# tivac-shield-communication.net
KiCad netlist of a schematic drawn in EAGLE
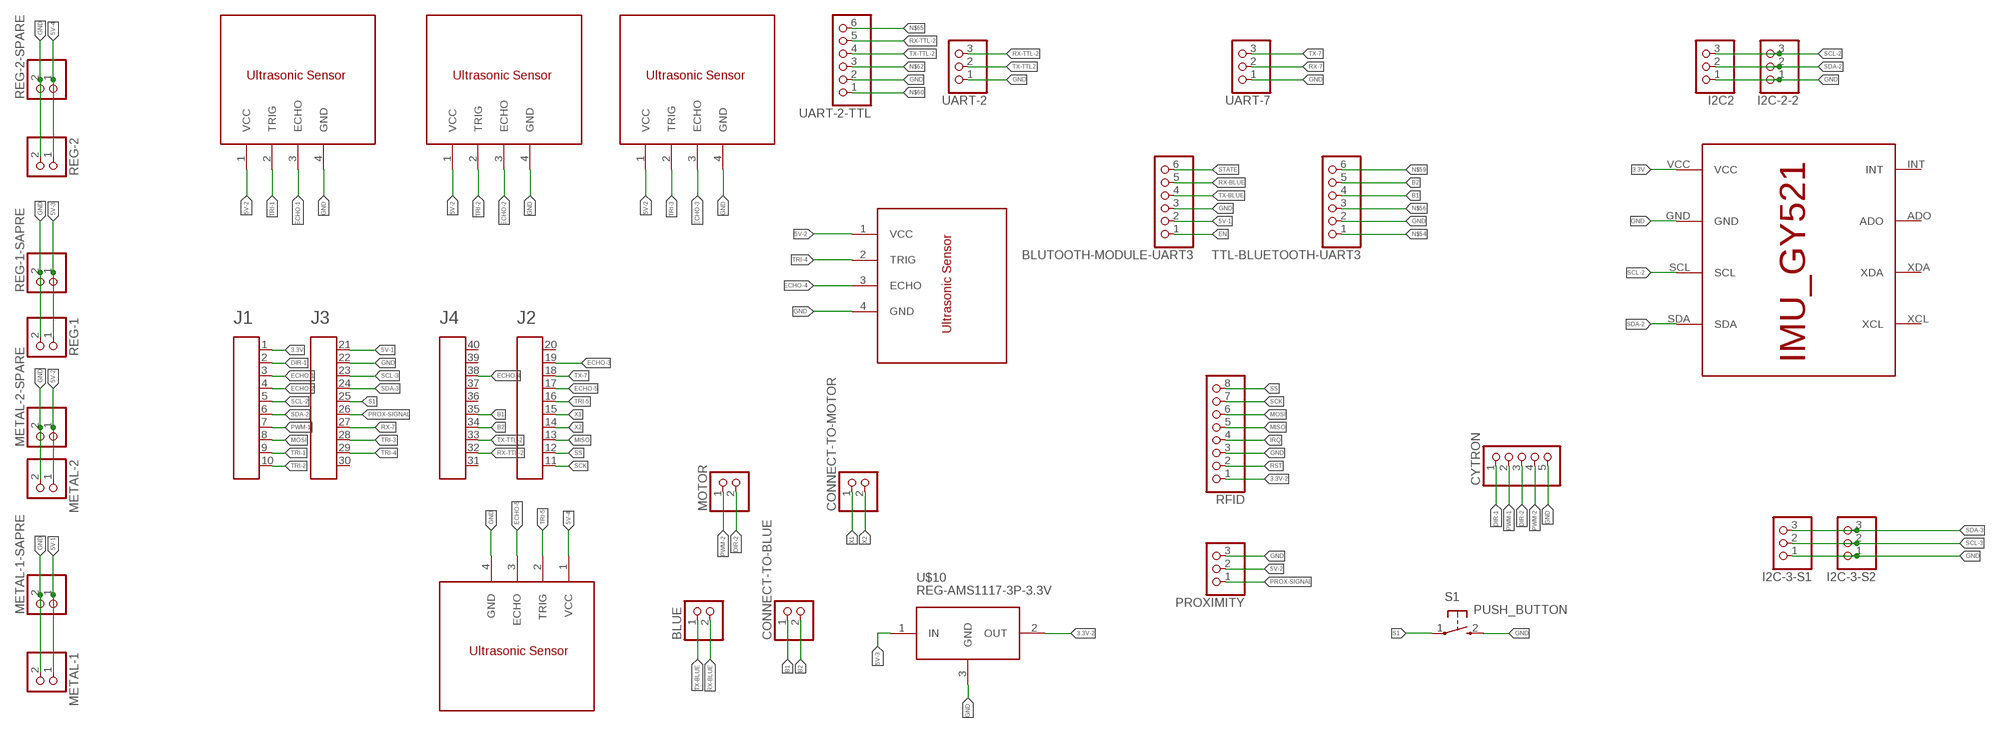
[diagram p0: schematic, sheet 1]

(export (version "E")
  (design (tool "Eeschema 10.0.6"))
  (components
    (comp (ref "A1")
      (value "HEADER4X10-BOOSTERPACK")
      (footprint "eagle-import:4X10-BOOSTERPACK")
      (libsource (lib "eagle-import") (part "HEADER4X10-BOOSTERPACK"))
    )
    (comp (ref "BLUE")
      (value "PINHD-2_DATA")
      (footprint "eagle-import:1X02_DATA")
      (libsource (lib "eagle-import") (part "PINHD-2_DATA"))
    )
    (comp (ref "BLUTOOTH-MODULE-UART3")
      (value "PINHD-1X6")
      (footprint "eagle-import:1X06")
      (libsource (lib "eagle-import") (part "PINHD-1X6"))
    )
    (comp (ref "CONNECT-TO-BLUE")
      (value "PINHD-2_DATA")
      (footprint "eagle-import:1X02_DATA")
      (libsource (lib "eagle-import") (part "PINHD-2_DATA"))
    )
    (comp (ref "CONNECT-TO-MOTOR")
      (value "PINHD-2_DATA")
      (footprint "eagle-import:1X02_DATA")
      (libsource (lib "eagle-import") (part "PINHD-2_DATA"))
    )
    (comp (ref "CYTRON")
      (value "PINHD-5_DATA")
      (footprint "eagle-import:1X05_DATA")
      (libsource (lib "eagle-import") (part "PINHD-5_DATA"))
    )
    (comp (ref "I2C-2-2")
      (value "PINHD-1X3")
      (footprint "eagle-import:1X03")
      (libsource (lib "eagle-import") (part "PINHD-1X3"))
    )
    (comp (ref "I2C-3-S1")
      (value "PINHD-1X3")
      (footprint "eagle-import:1X03")
      (libsource (lib "eagle-import") (part "PINHD-1X3"))
    )
    (comp (ref "I2C-3-S2")
      (value "PINHD-1X3")
      (footprint "eagle-import:1X03")
      (libsource (lib "eagle-import") (part "PINHD-1X3"))
    )
    (comp (ref "I2C2")
      (value "PINHD-1X3")
      (footprint "eagle-import:1X03")
      (libsource (lib "eagle-import") (part "PINHD-1X3"))
    )
    (comp (ref "METAL-1")
      (value "PINHD-1X2")
      (footprint "eagle-import:1X02")
      (libsource (lib "eagle-import") (part "PINHD-1X2"))
    )
    (comp (ref "METAL-1-SAPRE")
      (value "PINHD-1X2")
      (footprint "eagle-import:1X02")
      (libsource (lib "eagle-import") (part "PINHD-1X2"))
    )
    (comp (ref "METAL-2")
      (value "PINHD-1X2")
      (footprint "eagle-import:1X02")
      (libsource (lib "eagle-import") (part "PINHD-1X2"))
    )
    (comp (ref "METAL-2-SPARE")
      (value "PINHD-1X2")
      (footprint "eagle-import:1X02")
      (libsource (lib "eagle-import") (part "PINHD-1X2"))
    )
    (comp (ref "MOTOR")
      (value "PINHD-2_DATA")
      (footprint "eagle-import:1X02_DATA")
      (libsource (lib "eagle-import") (part "PINHD-2_DATA"))
    )
    (comp (ref "PROXIMITY")
      (value "PINHD-1X3")
      (footprint "eagle-import:1X03")
      (libsource (lib "eagle-import") (part "PINHD-1X3"))
    )
    (comp (ref "REG-1")
      (value "PINHD-1X2")
      (footprint "eagle-import:1X02")
      (libsource (lib "eagle-import") (part "PINHD-1X2"))
    )
    (comp (ref "REG-1-SAPRE")
      (value "PINHD-1X2")
      (footprint "eagle-import:1X02")
      (libsource (lib "eagle-import") (part "PINHD-1X2"))
    )
    (comp (ref "REG-2")
      (value "PINHD-1X2")
      (footprint "eagle-import:1X02")
      (libsource (lib "eagle-import") (part "PINHD-1X2"))
    )
    (comp (ref "REG-2-SPARE")
      (value "PINHD-1X2")
      (footprint "eagle-import:1X02")
      (libsource (lib "eagle-import") (part "PINHD-1X2"))
    )
    (comp (ref "RFID")
      (value "PINHD-1X8")
      (footprint "eagle-import:1X08")
      (libsource (lib "eagle-import") (part "PINHD-1X8"))
    )
    (comp (ref "S1")
      (value "PUSH_BUTTON")
      (footprint "eagle-import:B3F-10XX")
      (libsource (lib "eagle-import") (part "PUSH_BUTTON"))
    )
    (comp (ref "TTL-BLUETOOTH-UART3")
      (value "PINHD-6_DATA")
      (footprint "eagle-import:1X06_DATA")
      (libsource (lib "eagle-import") (part "PINHD-6_DATA"))
    )
    (comp (ref "U$1")
      (value "ULTRASONIC_SENSOR")
      (footprint "eagle-import:1X04")
      (libsource (lib "eagle-import") (part "ULTRASONIC_SENSOR"))
    )
    (comp (ref "U$2")
      (value "ULTRASONIC_SENSOR")
      (footprint "eagle-import:1X04")
      (libsource (lib "eagle-import") (part "ULTRASONIC_SENSOR"))
    )
    (comp (ref "U$3")
      (value "ULTRASONIC_SENSOR")
      (footprint "eagle-import:1X04")
      (libsource (lib "eagle-import") (part "ULTRASONIC_SENSOR"))
    )
    (comp (ref "U$5")
      (value "ULTRASONIC_SENSOR")
      (footprint "eagle-import:1X04")
      (libsource (lib "eagle-import") (part "ULTRASONIC_SENSOR"))
    )
    (comp (ref "U$7")
      (value "ULTRASONIC_SENSOR")
      (footprint "eagle-import:1X04")
      (libsource (lib "eagle-import") (part "ULTRASONIC_SENSOR"))
    )
    (comp (ref "U$9")
      (value "IMU_ROBOCON")
      (footprint "eagle-import:IMU_GY521")
      (libsource (lib "eagle-import") (part "IMU_ROBOCON"))
    )
    (comp (ref "U$10")
      (value "REG-AMS1117-3P-3.3V")
      (footprint "eagle-import:REG-AMS1117-3P")
      (libsource (lib "eagle-import") (part "REG-AMS1117-3P-3.3V"))
    )
    (comp (ref "UART-2")
      (value "PINHD-1X3")
      (footprint "eagle-import:1X03")
      (libsource (lib "eagle-import") (part "PINHD-1X3"))
    )
    (comp (ref "UART-2-TTL")
      (value "PINHD-6_DATA")
      (footprint "eagle-import:1X06_DATA")
      (libsource (lib "eagle-import") (part "PINHD-6_DATA"))
    )
    (comp (ref "UART-7")
      (value "PINHD-1X3")
      (footprint "eagle-import:1X03")
      (libsource (lib "eagle-import") (part "PINHD-1X3"))
    )
  )
  (nets
    (net (code "1") (name "3.3V") (class "Default")
      (node (ref "A1") (pin "1") (pinfunction "P$1_1") (pintype "bidirectional"))
      (node (ref "U$9") (pin "VCC") (pinfunction "VCC_VCC") (pintype "bidirectional"))
    )
    (net (code "2") (name "3.3V-2") (class "Default")
      (node (ref "RFID") (pin "1") (pinfunction "1_1") (pintype "passive"))
      (node (ref "U$10") (pin "2") (pinfunction "OUT_2") (pintype "bidirectional"))
    )
    (net (code "3") (name "5V-1") (class "Default")
      (node (ref "A1") (pin "21") (pinfunction "P$21_21") (pintype "bidirectional"))
      (node (ref "BLUTOOTH-MODULE-UART3") (pin "2") (pinfunction "2_2") (pintype "passive"))
      (node (ref "METAL-1") (pin "1") (pinfunction "1_1") (pintype "passive"))
      (node (ref "METAL-1-SAPRE") (pin "1") (pinfunction "1_1") (pintype "passive"))
    )
    (net (code "4") (name "5V-2") (class "Default")
      (node (ref "METAL-2") (pin "1") (pinfunction "1_1") (pintype "passive"))
      (node (ref "METAL-2-SPARE") (pin "1") (pinfunction "1_1") (pintype "passive"))
      (node (ref "PROXIMITY") (pin "2") (pinfunction "2_2") (pintype "passive"))
      (node (ref "U$1") (pin "1") (pinfunction "VCC_1") (pintype "bidirectional"))
      (node (ref "U$2") (pin "1") (pinfunction "VCC_1") (pintype "bidirectional"))
      (node (ref "U$3") (pin "1") (pinfunction "VCC_1") (pintype "bidirectional"))
      (node (ref "U$7") (pin "1") (pinfunction "VCC_1") (pintype "bidirectional"))
    )
    (net (code "5") (name "5V-3") (class "Default")
      (node (ref "REG-1") (pin "1") (pinfunction "1_1") (pintype "passive"))
      (node (ref "REG-1-SAPRE") (pin "1") (pinfunction "1_1") (pintype "passive"))
      (node (ref "U$10") (pin "1") (pinfunction "IN_1") (pintype "bidirectional"))
    )
    (net (code "6") (name "5V-4") (class "Default")
      (node (ref "REG-2") (pin "1") (pinfunction "1_1") (pintype "passive"))
      (node (ref "REG-2-SPARE") (pin "1") (pinfunction "1_1") (pintype "passive"))
      (node (ref "U$5") (pin "1") (pinfunction "VCC_1") (pintype "bidirectional"))
    )
    (net (code "7") (name "B1") (class "Default")
      (node (ref "A1") (pin "35") (pinfunction "P$35_35") (pintype "bidirectional"))
      (node (ref "CONNECT-TO-BLUE") (pin "1") (pinfunction "1_1") (pintype "passive"))
      (node (ref "TTL-BLUETOOTH-UART3") (pin "4") (pinfunction "4_4") (pintype "passive"))
    )
    (net (code "8") (name "B2") (class "Default")
      (node (ref "A1") (pin "34") (pinfunction "P$34_34") (pintype "bidirectional"))
      (node (ref "CONNECT-TO-BLUE") (pin "2") (pinfunction "2_2") (pintype "passive"))
      (node (ref "TTL-BLUETOOTH-UART3") (pin "5") (pinfunction "5_5") (pintype "passive"))
    )
    (net (code "9") (name "DIR-1") (class "Default")
      (node (ref "A1") (pin "2") (pinfunction "P$2_2") (pintype "bidirectional"))
      (node (ref "CYTRON") (pin "1") (pinfunction "1_1") (pintype "passive"))
    )
    (net (code "10") (name "DIR-2") (class "Default")
      (node (ref "CYTRON") (pin "3") (pinfunction "3_3") (pintype "passive"))
      (node (ref "MOTOR") (pin "2") (pinfunction "2_2") (pintype "passive"))
    )
    (net (code "11") (name "ECHO-1") (class "Default")
      (node (ref "A1") (pin "3") (pinfunction "P$3_3") (pintype "bidirectional"))
      (node (ref "U$1") (pin "3") (pinfunction "ECHO_3") (pintype "bidirectional"))
    )
    (net (code "12") (name "ECHO-2") (class "Default")
      (node (ref "A1") (pin "4") (pinfunction "P$4_4") (pintype "bidirectional"))
      (node (ref "U$2") (pin "3") (pinfunction "ECHO_3") (pintype "bidirectional"))
    )
    (net (code "13") (name "ECHO-3") (class "Default")
      (node (ref "A1") (pin "19") (pinfunction "P$19_19") (pintype "bidirectional"))
      (node (ref "U$3") (pin "3") (pinfunction "ECHO_3") (pintype "bidirectional"))
    )
    (net (code "14") (name "ECHO-4") (class "Default")
      (node (ref "A1") (pin "38") (pinfunction "P$38_38") (pintype "bidirectional"))
      (node (ref "U$7") (pin "3") (pinfunction "ECHO_3") (pintype "bidirectional"))
    )
    (net (code "15") (name "ECHO-5") (class "Default")
      (node (ref "A1") (pin "17") (pinfunction "P$17_17") (pintype "bidirectional"))
      (node (ref "U$5") (pin "3") (pinfunction "ECHO_3") (pintype "bidirectional"))
    )
    (net (code "16") (name "EN") (class "Default")
      (node (ref "BLUTOOTH-MODULE-UART3") (pin "1") (pinfunction "1_1") (pintype "passive"))
    )
    (net (code "17") (name "GND") (class "Default")
      (node (ref "A1") (pin "22") (pinfunction "P$22_22") (pintype "bidirectional"))
      (node (ref "BLUTOOTH-MODULE-UART3") (pin "3") (pinfunction "3_3") (pintype "passive"))
      (node (ref "CYTRON") (pin "5") (pinfunction "5_5") (pintype "passive"))
      (node (ref "I2C-2-2") (pin "1") (pinfunction "1_1") (pintype "passive"))
      (node (ref "I2C-3-S1") (pin "1") (pinfunction "1_1") (pintype "passive"))
      (node (ref "I2C-3-S2") (pin "1") (pinfunction "1_1") (pintype "passive"))
      (node (ref "I2C2") (pin "1") (pinfunction "1_1") (pintype "passive"))
      (node (ref "METAL-1") (pin "2") (pinfunction "2_2") (pintype "passive"))
      (node (ref "METAL-1-SAPRE") (pin "2") (pinfunction "2_2") (pintype "passive"))
      (node (ref "METAL-2") (pin "2") (pinfunction "2_2") (pintype "passive"))
      (node (ref "METAL-2-SPARE") (pin "2") (pinfunction "2_2") (pintype "passive"))
      (node (ref "PROXIMITY") (pin "3") (pinfunction "3_3") (pintype "passive"))
      (node (ref "REG-1") (pin "2") (pinfunction "2_2") (pintype "passive"))
      (node (ref "REG-1-SAPRE") (pin "2") (pinfunction "2_2") (pintype "passive"))
      (node (ref "REG-2") (pin "2") (pinfunction "2_2") (pintype "passive"))
      (node (ref "REG-2-SPARE") (pin "2") (pinfunction "2_2") (pintype "passive"))
      (node (ref "RFID") (pin "3") (pinfunction "3_3") (pintype "passive"))
      (node (ref "S1") (pin "2") (pinfunction "S_2") (pintype "passive"))
      (node (ref "TTL-BLUETOOTH-UART3") (pin "2") (pinfunction "2_2") (pintype "passive"))
      (node (ref "U$1") (pin "4") (pinfunction "GND_4") (pintype "bidirectional"))
      (node (ref "U$10") (pin "3") (pinfunction "GND_3") (pintype "bidirectional"))
      (node (ref "U$2") (pin "4") (pinfunction "GND_4") (pintype "bidirectional"))
      (node (ref "U$3") (pin "4") (pinfunction "GND_4") (pintype "bidirectional"))
      (node (ref "U$5") (pin "4") (pinfunction "GND_4") (pintype "bidirectional"))
      (node (ref "U$7") (pin "4") (pinfunction "GND_4") (pintype "bidirectional"))
      (node (ref "U$9") (pin "GND") (pinfunction "GND_GND") (pintype "bidirectional"))
      (node (ref "UART-2") (pin "1") (pinfunction "1_1") (pintype "passive"))
      (node (ref "UART-2-TTL") (pin "2") (pinfunction "2_2") (pintype "passive"))
      (node (ref "UART-7") (pin "1") (pinfunction "1_1") (pintype "passive"))
    )
    (net (code "18") (name "IRQ") (class "Default")
      (node (ref "RFID") (pin "4") (pinfunction "4_4") (pintype "passive"))
    )
    (net (code "19") (name "MISO") (class "Default")
      (node (ref "A1") (pin "13") (pinfunction "P$13_13") (pintype "bidirectional"))
      (node (ref "RFID") (pin "5") (pinfunction "5_5") (pintype "passive"))
    )
    (net (code "20") (name "MOSI") (class "Default")
      (node (ref "A1") (pin "8") (pinfunction "P$8_8") (pintype "bidirectional"))
      (node (ref "RFID") (pin "6") (pinfunction "6_6") (pintype "passive"))
    )
    (net (code "21") (name "N$54") (class "Default")
      (node (ref "TTL-BLUETOOTH-UART3") (pin "1") (pinfunction "1_1") (pintype "passive"))
    )
    (net (code "22") (name "N$56") (class "Default")
      (node (ref "TTL-BLUETOOTH-UART3") (pin "3") (pinfunction "3_3") (pintype "passive"))
    )
    (net (code "23") (name "N$59") (class "Default")
      (node (ref "TTL-BLUETOOTH-UART3") (pin "6") (pinfunction "6_6") (pintype "passive"))
    )
    (net (code "24") (name "N$60") (class "Default")
      (node (ref "UART-2-TTL") (pin "1") (pinfunction "1_1") (pintype "passive"))
    )
    (net (code "25") (name "N$62") (class "Default")
      (node (ref "UART-2-TTL") (pin "3") (pinfunction "3_3") (pintype "passive"))
    )
    (net (code "26") (name "N$65") (class "Default")
      (node (ref "UART-2-TTL") (pin "6") (pinfunction "6_6") (pintype "passive"))
    )
    (net (code "27") (name "PROX-SIGNAL") (class "Default")
      (node (ref "A1") (pin "26") (pinfunction "P$26_26") (pintype "bidirectional"))
      (node (ref "PROXIMITY") (pin "1") (pinfunction "1_1") (pintype "passive"))
    )
    (net (code "28") (name "PWM-1") (class "Default")
      (node (ref "A1") (pin "7") (pinfunction "P$7_7") (pintype "bidirectional"))
      (node (ref "CYTRON") (pin "2") (pinfunction "2_2") (pintype "passive"))
    )
    (net (code "29") (name "PWM-2") (class "Default")
      (node (ref "CYTRON") (pin "4") (pinfunction "4_4") (pintype "passive"))
      (node (ref "MOTOR") (pin "1") (pinfunction "1_1") (pintype "passive"))
    )
    (net (code "30") (name "RST") (class "Default")
      (node (ref "RFID") (pin "2") (pinfunction "2_2") (pintype "passive"))
    )
    (net (code "31") (name "RX-7") (class "Default")
      (node (ref "A1") (pin "27") (pinfunction "P$27_27") (pintype "bidirectional"))
      (node (ref "UART-7") (pin "2") (pinfunction "2_2") (pintype "passive"))
    )
    (net (code "32") (name "RX-BLUE") (class "Default")
      (node (ref "BLUE") (pin "2") (pinfunction "2_2") (pintype "passive"))
      (node (ref "BLUTOOTH-MODULE-UART3") (pin "5") (pinfunction "5_5") (pintype "passive"))
    )
    (net (code "33") (name "RX-TTL-2") (class "Default")
      (node (ref "A1") (pin "32") (pinfunction "P$32_32") (pintype "bidirectional"))
      (node (ref "UART-2") (pin "3") (pinfunction "3_3") (pintype "passive"))
      (node (ref "UART-2-TTL") (pin "5") (pinfunction "5_5") (pintype "passive"))
    )
    (net (code "34") (name "S1") (class "Default")
      (node (ref "A1") (pin "25") (pinfunction "P$25_25") (pintype "bidirectional"))
      (node (ref "S1") (pin "1") (pinfunction "P_1") (pintype "passive"))
    )
    (net (code "35") (name "SCK") (class "Default")
      (node (ref "A1") (pin "11") (pinfunction "P$11_11") (pintype "bidirectional"))
      (node (ref "RFID") (pin "7") (pinfunction "7_7") (pintype "passive"))
    )
    (net (code "36") (name "SCL-2") (class "Default")
      (node (ref "A1") (pin "5") (pinfunction "P$5_5") (pintype "bidirectional"))
      (node (ref "I2C-2-2") (pin "3") (pinfunction "3_3") (pintype "passive"))
      (node (ref "I2C2") (pin "3") (pinfunction "3_3") (pintype "passive"))
      (node (ref "U$9") (pin "SCL") (pinfunction "SCL_SCL") (pintype "bidirectional"))
    )
    (net (code "37") (name "SCL-3") (class "Default")
      (node (ref "A1") (pin "23") (pinfunction "P$23_23") (pintype "bidirectional"))
      (node (ref "I2C-3-S1") (pin "2") (pinfunction "2_2") (pintype "passive"))
      (node (ref "I2C-3-S2") (pin "2") (pinfunction "2_2") (pintype "passive"))
    )
    (net (code "38") (name "SDA-2") (class "Default")
      (node (ref "A1") (pin "6") (pinfunction "P$6_6") (pintype "bidirectional"))
      (node (ref "I2C-2-2") (pin "2") (pinfunction "2_2") (pintype "passive"))
      (node (ref "I2C2") (pin "2") (pinfunction "2_2") (pintype "passive"))
      (node (ref "U$9") (pin "SDA") (pinfunction "SDA_SDA") (pintype "bidirectional"))
    )
    (net (code "39") (name "SDA-3") (class "Default")
      (node (ref "A1") (pin "24") (pinfunction "P$24_24") (pintype "bidirectional"))
      (node (ref "I2C-3-S1") (pin "3") (pinfunction "3_3") (pintype "passive"))
      (node (ref "I2C-3-S2") (pin "3") (pinfunction "3_3") (pintype "passive"))
    )
    (net (code "40") (name "SS") (class "Default")
      (node (ref "A1") (pin "12") (pinfunction "P$12_12") (pintype "bidirectional"))
      (node (ref "RFID") (pin "8") (pinfunction "8_8") (pintype "passive"))
    )
    (net (code "41") (name "STATE") (class "Default")
      (node (ref "BLUTOOTH-MODULE-UART3") (pin "6") (pinfunction "6_6") (pintype "passive"))
    )
    (net (code "42") (name "TRI-1") (class "Default")
      (node (ref "A1") (pin "9") (pinfunction "P$9_9") (pintype "bidirectional"))
      (node (ref "U$1") (pin "2") (pinfunction "TRIG_2") (pintype "bidirectional"))
    )
    (net (code "43") (name "TRI-2") (class "Default")
      (node (ref "A1") (pin "10") (pinfunction "P$10_10") (pintype "bidirectional"))
      (node (ref "U$2") (pin "2") (pinfunction "TRIG_2") (pintype "bidirectional"))
    )
    (net (code "44") (name "TRI-3") (class "Default")
      (node (ref "A1") (pin "28") (pinfunction "P$28_28") (pintype "bidirectional"))
      (node (ref "U$3") (pin "2") (pinfunction "TRIG_2") (pintype "bidirectional"))
    )
    (net (code "45") (name "TRI-4") (class "Default")
      (node (ref "A1") (pin "29") (pinfunction "P$29_29") (pintype "bidirectional"))
      (node (ref "U$7") (pin "2") (pinfunction "TRIG_2") (pintype "bidirectional"))
    )
    (net (code "46") (name "TRI-5") (class "Default")
      (node (ref "A1") (pin "16") (pinfunction "P$16_16") (pintype "bidirectional"))
      (node (ref "U$5") (pin "2") (pinfunction "TRIG_2") (pintype "bidirectional"))
    )
    (net (code "47") (name "TX-7") (class "Default")
      (node (ref "A1") (pin "18") (pinfunction "P$18_18") (pintype "bidirectional"))
      (node (ref "UART-7") (pin "3") (pinfunction "3_3") (pintype "passive"))
    )
    (net (code "48") (name "TX-BLUE") (class "Default")
      (node (ref "BLUE") (pin "1") (pinfunction "1_1") (pintype "passive"))
      (node (ref "BLUTOOTH-MODULE-UART3") (pin "4") (pinfunction "4_4") (pintype "passive"))
    )
    (net (code "49") (name "TX-TTL-2") (class "Default")
      (node (ref "A1") (pin "33") (pinfunction "P$33_33") (pintype "bidirectional"))
      (node (ref "UART-2-TTL") (pin "4") (pinfunction "4_4") (pintype "passive"))
    )
    (net (code "50") (name "TX-TTL2") (class "Default")
      (node (ref "UART-2") (pin "2") (pinfunction "2_2") (pintype "passive"))
    )
    (net (code "51") (name "X1") (class "Default")
      (node (ref "A1") (pin "15") (pinfunction "P$15_15") (pintype "bidirectional"))
      (node (ref "CONNECT-TO-MOTOR") (pin "1") (pinfunction "1_1") (pintype "passive"))
    )
    (net (code "52") (name "X2") (class "Default")
      (node (ref "A1") (pin "14") (pinfunction "P$14_14") (pintype "bidirectional"))
      (node (ref "CONNECT-TO-MOTOR") (pin "2") (pinfunction "2_2") (pintype "passive"))
    )
    (net (code "53") (name "unconnected-(A1-P$20-Pad20)") (class "Default")
      (node (ref "A1") (pin "20") (pinfunction "P$20_20") (pintype "bidirectional"))
    )
    (net (code "54") (name "unconnected-(A1-P$30-Pad30)") (class "Default")
      (node (ref "A1") (pin "30") (pinfunction "P$30_30") (pintype "bidirectional"))
    )
    (net (code "55") (name "unconnected-(A1-P$31-Pad31)") (class "Default")
      (node (ref "A1") (pin "31") (pinfunction "P$31_31") (pintype "bidirectional"))
    )
    (net (code "56") (name "unconnected-(A1-P$36-Pad36)") (class "Default")
      (node (ref "A1") (pin "36") (pinfunction "P$36_36") (pintype "bidirectional"))
    )
    (net (code "57") (name "unconnected-(A1-P$37-Pad37)") (class "Default")
      (node (ref "A1") (pin "37") (pinfunction "P$37_37") (pintype "bidirectional"))
    )
    (net (code "58") (name "unconnected-(A1-P$39-Pad39)") (class "Default")
      (node (ref "A1") (pin "39") (pinfunction "P$39_39") (pintype "bidirectional"))
    )
    (net (code "59") (name "unconnected-(A1-P$40-Pad40)") (class "Default")
      (node (ref "A1") (pin "40") (pinfunction "P$40_40") (pintype "bidirectional"))
    )
    (net (code "60") (name "unconnected-(U$9-PadADO)") (class "Default")
      (node (ref "U$9") (pin "ADO") (pinfunction "ADO_ADO") (pintype "bidirectional"))
    )
    (net (code "61") (name "unconnected-(U$9-PadINT)") (class "Default")
      (node (ref "U$9") (pin "INT") (pinfunction "INT_INT") (pintype "bidirectional"))
    )
    (net (code "62") (name "unconnected-(U$9-PadXCL)") (class "Default")
      (node (ref "U$9") (pin "XCL") (pinfunction "XCL_XCL") (pintype "bidirectional"))
    )
    (net (code "63") (name "unconnected-(U$9-PadXDA)") (class "Default")
      (node (ref "U$9") (pin "XDA") (pinfunction "XDA_XDA") (pintype "bidirectional"))
    )
  )
)
